# HT66FM5440_EVB.net
KiCad netlist of a schematic drawn in Altium Designer
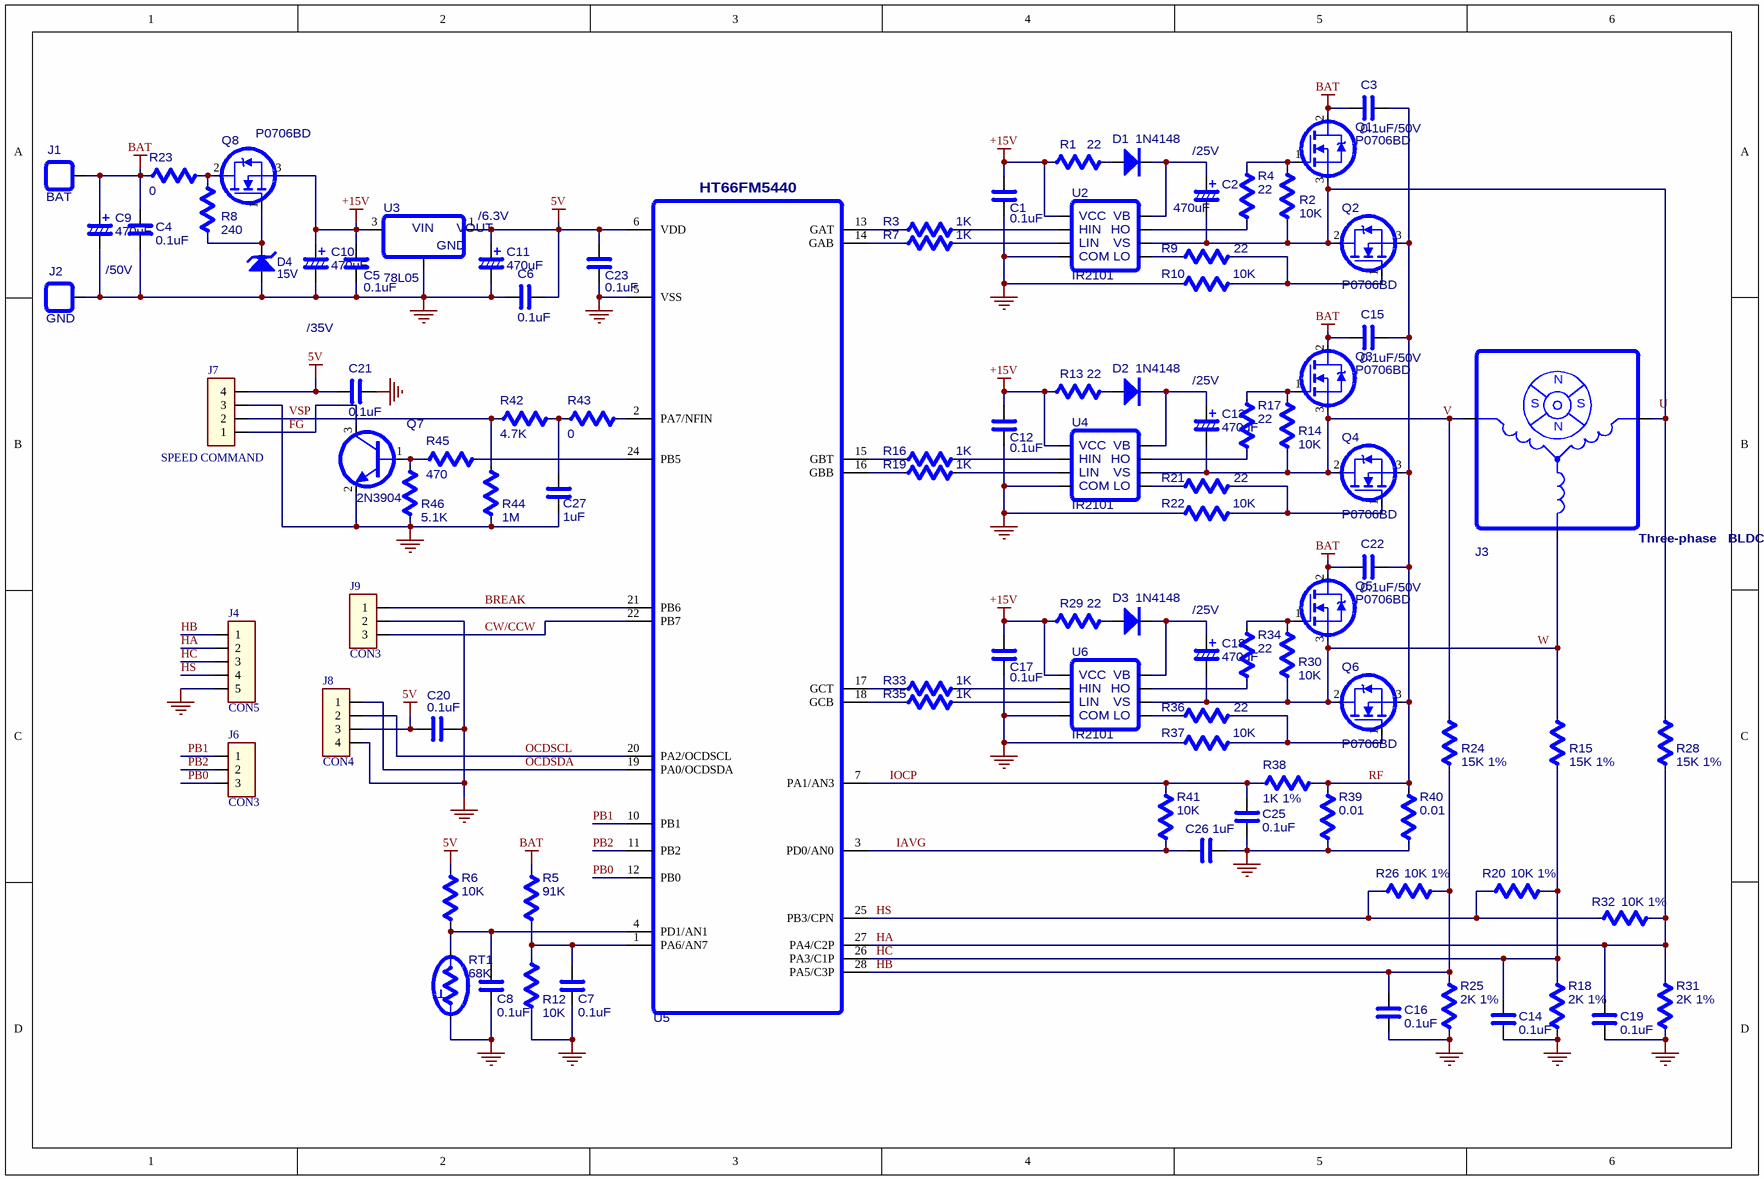
[diagram p0: HT66FM5440_EVB.SchDoc]

(export (version "E")
  (design (tool "Eeschema 10.0.6"))
  (components
    (comp (ref "C1")
      (value "0.1uF")
      (description "Capacitor")
      (fields (field (name "PUBLISHER") "Altium Limited"))
      (libsource (lib "Holtek Component Library V2") (part "Cap(1)"))
    )
    (comp (ref "C2")
      (value "470uF")
      (footprint "0805C")
      (description "Capacitor")
      (libsource (lib "C70005") (part "Cap(2)"))
    )
    (comp (ref "C3")
      (value "0.1uF/50V")
      (description "Capacitor")
      (fields (field (name "PUBLISHER") "Altium Limited"))
      (libsource (lib "Holtek Component Library V2") (part "Cap(1)"))
    )
    (comp (ref "C4")
      (value "0.1uF")
      (description "Capacitor")
      (fields (field (name "PUBLISHER") "Altium Limited"))
      (libsource (lib "Holtek Component Library V2") (part "Cap(1)"))
    )
    (comp (ref "C5")
      (value "0.1uF")
      (description "Capacitor")
      (fields (field (name "PUBLISHER") "Altium Limited"))
      (libsource (lib "Holtek Component Library V2") (part "Cap(1)"))
    )
    (comp (ref "C6")
      (value "0.1uF")
      (description "Capacitor")
      (fields (field (name "PUBLISHER") "Altium Limited"))
      (libsource (lib "Holtek Component Library V2") (part "Cap(1)"))
    )
    (comp (ref "C7")
      (value "0.1uF")
      (description "Capacitor")
      (fields (field (name "PUBLISHER") "Altium Limited"))
      (libsource (lib "Holtek Component Library V2") (part "Cap(1)"))
    )
    (comp (ref "C8")
      (value "0.1uF")
      (description "Capacitor")
      (fields (field (name "PUBLISHER") "Altium Limited"))
      (libsource (lib "Holtek Component Library V2") (part "Cap(1)"))
    )
    (comp (ref "C9")
      (value "470uF")
      (footprint "CD-10.5*21")
      (description "Capacitor")
      (libsource (lib "C70005") (part "Cap(2)"))
    )
    (comp (ref "C10")
      (value "470uF")
      (footprint "ECAP 35V47UF")
      (description "Capacitor")
      (libsource (lib "C70005") (part "Cap(2)"))
    )
    (comp (ref "C11")
      (value "470uF")
      (footprint "ECAP 35V47UF")
      (description "Capacitor")
      (libsource (lib "C70005") (part "Cap(2)"))
    )
    (comp (ref "C12")
      (value "0.1uF")
      (description "Capacitor")
      (fields (field (name "PUBLISHER") "Altium Limited"))
      (libsource (lib "Holtek Component Library V2") (part "Cap(1)"))
    )
    (comp (ref "C13")
      (value "470uF")
      (footprint "0805C")
      (description "Capacitor")
      (libsource (lib "C70005") (part "Cap(2)"))
    )
    (comp (ref "C14")
      (value "0.1uF")
      (footprint "0603C")
      (description "Capacitor")
      (fields (field (name "PUBLISHER") "Altium Limited"))
      (libsource (lib "Holtek Component Library V2") (part "Cap(1)"))
    )
    (comp (ref "C15")
      (value "0.1uF/50V")
      (description "Capacitor")
      (fields (field (name "PUBLISHER") "Altium Limited"))
      (libsource (lib "Holtek Component Library V2") (part "Cap(1)"))
    )
    (comp (ref "C16")
      (value "0.1uF")
      (footprint "0603C")
      (description "Capacitor")
      (fields (field (name "PUBLISHER") "Altium Limited"))
      (libsource (lib "Holtek Component Library V2") (part "Cap(1)"))
    )
    (comp (ref "C17")
      (value "0.1uF")
      (description "Capacitor")
      (fields (field (name "PUBLISHER") "Altium Limited"))
      (libsource (lib "Holtek Component Library V2") (part "Cap(1)"))
    )
    (comp (ref "C18")
      (value "470uF")
      (footprint "0805C")
      (description "Capacitor")
      (libsource (lib "C70005") (part "Cap(2)"))
    )
    (comp (ref "C19")
      (value "0.1uF")
      (footprint "0603C")
      (description "Capacitor")
      (fields (field (name "PUBLISHER") "Altium Limited"))
      (libsource (lib "Holtek Component Library V2") (part "Cap(1)"))
    )
    (comp (ref "C20")
      (value "0.1uF")
      (footprint "0603c")
      (description "Capacitor")
      (fields (field (name "PUBLISHER") "Altium Limited"))
      (libsource (lib "Holtek Component Library V2") (part "Cap(1)"))
    )
    (comp (ref "C21")
      (value "0.1uF")
      (footprint "0603c")
      (description "Capacitor")
      (fields (field (name "PUBLISHER") "Altium Limited"))
      (libsource (lib "Holtek Component Library V2") (part "Cap(1)"))
    )
    (comp (ref "C22")
      (value "0.1uF/50V")
      (description "Capacitor")
      (fields (field (name "PUBLISHER") "Altium Limited"))
      (libsource (lib "Holtek Component Library V2") (part "Cap(1)"))
    )
    (comp (ref "C23")
      (value "0.1uF")
      (description "Capacitor")
      (fields (field (name "PUBLISHER") "Altium Limited"))
      (libsource (lib "Holtek Component Library V2") (part "Cap(1)"))
    )
    (comp (ref "C25")
      (value "0.1uF")
      (description "Capacitor")
      (fields (field (name "PUBLISHER") "Altium Limited"))
      (libsource (lib "Holtek Component Library V2") (part "Cap(1)"))
    )
    (comp (ref "C26")
      (value "1uF")
      (description "Capacitor")
      (fields (field (name "PUBLISHER") "Altium Limited"))
      (libsource (lib "Holtek Component Library V2") (part "Cap(1)"))
    )
    (comp (ref "C27")
      (value "1uF")
      (description "Capacitor")
      (fields (field (name "PUBLISHER") "Altium Limited"))
      (libsource (lib "Holtek Component Library V2") (part "Cap(1)"))
    )
    (comp (ref "D1")
      (value "1N4148")
      (footprint "1206D")
      (description "Diode")
      (fields (field (name "PUBLISHER") "Altium Limited"))
      (libsource (lib "Holtek Component Library V2") (part "Diode(1)"))
    )
    (comp (ref "D2")
      (value "1N4148")
      (footprint "1206D")
      (description "Diode")
      (fields (field (name "PUBLISHER") "Altium Limited"))
      (libsource (lib "Holtek Component Library V2") (part "Diode(1)"))
    )
    (comp (ref "D3")
      (value "1N4148")
      (footprint "1206D")
      (description "Diode")
      (fields (field (name "PUBLISHER") "Altium Limited"))
      (libsource (lib "Holtek Component Library V2") (part "Diode(1)"))
    )
    (comp (ref "D4")
      (value "15V")
      (footprint "1206D")
      (description "Zener Diode")
      (libsource (lib "Holtek Component Library V2(Chris)") (part "Zener(1)"))
    )
    (comp (ref "J1")
      (value "BAT")
      (footprint "SIP1-big")
      (description "CON1")
      (fields (field (name "PUBLISHER") "Altium Limited"))
      (libsource (lib "C70005-A1") (part "CON1"))
    )
    (comp (ref "J2")
      (value "GND")
      (footprint "SIP1-big")
      (description "CON1")
      (fields (field (name "PUBLISHER") "Altium Limited"))
      (libsource (lib "C70005-A1") (part "CON1"))
    )
    (comp (ref "J3") (value "BLDC motor(1)") (libsource (lib "C70005") (part "BLDC motor(1)_1")))
    (comp (ref "J4") (value "CON5") (libsource (lib "MYLIB") (part "CON5")))
    (comp (ref "J6") (value "CON3") (libsource (lib "") (part "CON3_1")))
    (comp (ref "J7") (value "SPEED COMMAND") (footprint "HDR1X4") (libsource (lib "MYLIB") (part "CON4")))
    (comp (ref "J8") (value "CON4") (footprint "SIP4") (libsource (lib "") (part "CON4_1")))
    (comp (ref "J9") (value "CON3") (footprint "SIP3-2.54mm") (libsource (lib "MYLIB") (part "CON3")))
    (comp (ref "Q1")
      (value "P0706BD")
      (footprint "TO252")
      (description "N-Channel Power MOSFET")
      (fields (field (name "PUBLISHER") "Altium Limited"))
      (libsource (lib "C70005") (part "NMOS(4)"))
    )
    (comp (ref "Q2")
      (value "P0706BD")
      (footprint "TO252")
      (description "N-Channel Power MOSFET")
      (fields (field (name "PUBLISHER") "Altium Limited"))
      (libsource (lib "C70005") (part "NMOS(4)"))
    )
    (comp (ref "Q3")
      (value "P0706BD")
      (footprint "TO252")
      (description "N-Channel Power MOSFET")
      (fields (field (name "PUBLISHER") "Altium Limited"))
      (libsource (lib "C70005") (part "NMOS(4)"))
    )
    (comp (ref "Q4")
      (value "P0706BD")
      (footprint "TO252")
      (description "N-Channel Power MOSFET")
      (fields (field (name "PUBLISHER") "Altium Limited"))
      (libsource (lib "C70005") (part "NMOS(4)"))
    )
    (comp (ref "Q5")
      (value "P0706BD")
      (footprint "TO252")
      (description "N-Channel Power MOSFET")
      (fields (field (name "PUBLISHER") "Altium Limited"))
      (libsource (lib "C70005") (part "NMOS(4)"))
    )
    (comp (ref "Q6")
      (value "P0706BD")
      (footprint "TO252")
      (description "N-Channel Power MOSFET")
      (fields (field (name "PUBLISHER") "Altium Limited"))
      (libsource (lib "C70005") (part "NMOS(4)"))
    )
    (comp (ref "Q7")
      (value "2N3904")
      (footprint "SOT-23")
      (description "NPN Bipolar Transistor")
      (fields (field (name "PUBLISHER") "Altium Limited"))
      (libsource (lib "C70005") (part "NPN(2)"))
    )
    (comp (ref "Q8")
      (value "P0706BD")
      (footprint "TO252")
      (description "N-Channel Power MOSFET")
      (fields (field (name "PUBLISHER") "Altium Limited"))
      (libsource (lib "C70005") (part "NMOS(4)"))
    )
    (comp (ref "R1")
      (value "22")
      (description "Resisitor")
      (libsource (lib "Holtek Component Library V2") (part "Resistor(1)_1"))
    )
    (comp (ref "R2")
      (value "10K")
      (description "Resisitor")
      (libsource (lib "Holtek Component Library V2") (part "Resistor(1)_1"))
    )
    (comp (ref "R3")
      (value "1K")
      (description "Resisitor")
      (libsource (lib "Holtek Component Library V2") (part "Resistor(1)_1"))
    )
    (comp (ref "R4")
      (value "22")
      (description "Resisitor")
      (libsource (lib "Holtek Component Library V2") (part "Resistor(1)_1"))
    )
    (comp (ref "R5")
      (value "91K")
      (description "Resisitor")
      (libsource (lib "Holtek Component Library V2") (part "Resistor(1)_1"))
    )
    (comp (ref "R6")
      (value "10K")
      (description "Resisitor")
      (libsource (lib "Holtek Component Library V2") (part "Resistor(1)_1"))
    )
    (comp (ref "R7")
      (value "1K")
      (description "Resisitor")
      (libsource (lib "Holtek Component Library V2") (part "Resistor(1)_1"))
    )
    (comp (ref "R8")
      (value "240")
      (description "Resisitor")
      (libsource (lib "Holtek Component Library V2") (part "Resistor(1)_1"))
    )
    (comp (ref "R9")
      (value "22")
      (description "Resisitor")
      (libsource (lib "Holtek Component Library V2") (part "Resistor(1)_1"))
    )
    (comp (ref "R10")
      (value "10K")
      (description "Resisitor")
      (libsource (lib "Holtek Component Library V2") (part "Resistor(1)_1"))
    )
    (comp (ref "R12")
      (value "10K")
      (description "Resisitor")
      (libsource (lib "Holtek Component Library V2") (part "Resistor(1)_1"))
    )
    (comp (ref "R13")
      (value "22")
      (description "Resisitor")
      (libsource (lib "Holtek Component Library V2") (part "Resistor(1)_1"))
    )
    (comp (ref "R14")
      (value "10K")
      (description "Resisitor")
      (libsource (lib "Holtek Component Library V2") (part "Resistor(1)_1"))
    )
    (comp (ref "R15")
      (value "15K 1%")
      (description "Resisitor")
      (libsource (lib "Holtek Component Library V2") (part "Resistor(1)_1"))
    )
    (comp (ref "R16")
      (value "1K")
      (description "Resisitor")
      (libsource (lib "Holtek Component Library V2") (part "Resistor(1)_1"))
    )
    (comp (ref "R17")
      (value "22")
      (description "Resisitor")
      (libsource (lib "Holtek Component Library V2") (part "Resistor(1)_1"))
    )
    (comp (ref "R18")
      (value "2K 1%")
      (description "Resisitor")
      (libsource (lib "Holtek Component Library V2") (part "Resistor(1)_1"))
    )
    (comp (ref "R19")
      (value "1K")
      (description "Resisitor")
      (libsource (lib "Holtek Component Library V2") (part "Resistor(1)_1"))
    )
    (comp (ref "R20")
      (value "10K 1%")
      (description "Resisitor")
      (libsource (lib "Holtek Component Library V2") (part "Resistor(1)_1"))
    )
    (comp (ref "R21")
      (value "22")
      (description "Resisitor")
      (libsource (lib "Holtek Component Library V2") (part "Resistor(1)_1"))
    )
    (comp (ref "R22")
      (value "10K")
      (description "Resisitor")
      (libsource (lib "Holtek Component Library V2") (part "Resistor(1)_1"))
    )
    (comp (ref "R23")
      (value "0")
      (description "Resisitor")
      (libsource (lib "Holtek Component Library V2") (part "Resistor(1)_1"))
    )
    (comp (ref "R24")
      (value "15K 1%")
      (description "Resisitor")
      (libsource (lib "Holtek Component Library V2") (part "Resistor(1)_1"))
    )
    (comp (ref "R25")
      (value "2K 1%")
      (description "Resisitor")
      (libsource (lib "Holtek Component Library V2") (part "Resistor(1)_1"))
    )
    (comp (ref "R26")
      (value "10K 1%")
      (description "Resisitor")
      (libsource (lib "Holtek Component Library V2") (part "Resistor(1)_1"))
    )
    (comp (ref "R28")
      (value "15K 1%")
      (description "Resisitor")
      (libsource (lib "Holtek Component Library V2") (part "Resistor(1)_1"))
    )
    (comp (ref "R29")
      (value "22")
      (description "Resisitor")
      (libsource (lib "Holtek Component Library V2") (part "Resistor(1)_1"))
    )
    (comp (ref "R30")
      (value "10K")
      (description "Resisitor")
      (libsource (lib "Holtek Component Library V2") (part "Resistor(1)_1"))
    )
    (comp (ref "R31")
      (value "2K 1%")
      (description "Resisitor")
      (libsource (lib "Holtek Component Library V2") (part "Resistor(1)_1"))
    )
    (comp (ref "R32")
      (value "10K 1%")
      (description "Resisitor")
      (libsource (lib "Holtek Component Library V2") (part "Resistor(1)_1"))
    )
    (comp (ref "R33")
      (value "1K")
      (description "Resisitor")
      (libsource (lib "Holtek Component Library V2") (part "Resistor(1)_1"))
    )
    (comp (ref "R34")
      (value "22")
      (description "Resisitor")
      (libsource (lib "Holtek Component Library V2") (part "Resistor(1)_1"))
    )
    (comp (ref "R35")
      (value "1K")
      (description "Resisitor")
      (libsource (lib "Holtek Component Library V2") (part "Resistor(1)_1"))
    )
    (comp (ref "R36")
      (value "22")
      (description "Resisitor")
      (libsource (lib "Holtek Component Library V2") (part "Resistor(1)_1"))
    )
    (comp (ref "R37")
      (value "10K")
      (description "Resisitor")
      (libsource (lib "Holtek Component Library V2") (part "Resistor(1)_1"))
    )
    (comp (ref "R38")
      (value "1K 1%")
      (description "Resisitor")
      (libsource (lib "Holtek Component Library V2") (part "Resistor(1)_1"))
    )
    (comp (ref "R39")
      (value "0.01")
      (description "Resisitor")
      (libsource (lib "Holtek Component Library V2") (part "Resistor(1)_1"))
    )
    (comp (ref "R40")
      (value "0.01")
      (description "Resisitor")
      (libsource (lib "Holtek Component Library V2") (part "Resistor(1)_1"))
    )
    (comp (ref "R41")
      (value "10K")
      (description "Resisitor")
      (libsource (lib "Holtek Component Library V2") (part "Resistor(1)_1"))
    )
    (comp (ref "R42")
      (value "4.7K")
      (description "Resisitor")
      (libsource (lib "Holtek Component Library V2") (part "Resistor(1)_1"))
    )
    (comp (ref "R43")
      (value "0")
      (description "Resisitor")
      (libsource (lib "Holtek Component Library V2") (part "Resistor(1)_1"))
    )
    (comp (ref "R44")
      (value "1M")
      (description "Resisitor")
      (libsource (lib "Holtek Component Library V2") (part "Resistor(1)_1"))
    )
    (comp (ref "R45")
      (value "470")
      (description "Resisitor")
      (libsource (lib "Holtek Component Library V2") (part "Resistor(1)_1"))
    )
    (comp (ref "R46")
      (value "5.1K")
      (description "Resisitor")
      (libsource (lib "Holtek Component Library V2") (part "Resistor(1)_1"))
    )
    (comp (ref "RT1") (value "68K") (libsource (lib "Holtek Component Library V2") (part "Sensor(1)")))
    (comp (ref "U2") (value "IR2101") (footprint "SOP-8") (libsource (lib "C70005") (part "IR2101/SOP-8")))
    (comp (ref "U3") (value "78L05") (footprint "SOT-89") (libsource (lib "C70005") (part "78L05_1")))
    (comp (ref "U4") (value "IR2101") (footprint "SOP-8") (libsource (lib "C70005") (part "IR2101/SOP-8")))
    (comp (ref "U5")
      (value "HT66FM5440/28SSOP")
      (footprint "SSOP28")
      (libsource (lib "C70005") (part "HT66FM5440/28SSOP"))
    )
    (comp (ref "U6") (value "IR2101") (footprint "SOP-8") (libsource (lib "C70005") (part "IR2101/SOP-8")))
  )
  (nets
    (net (code "1") (name "+15V") (class "Default")
      (node (ref "C1") (pin "2") (pinfunction "2_2") (pintype "passive"))
      (node (ref "C10") (pin "1") (pinfunction "1_1") (pintype "passive"))
      (node (ref "C12") (pin "2") (pinfunction "2_2") (pintype "passive"))
      (node (ref "C17") (pin "2") (pinfunction "2_2") (pintype "passive"))
      (node (ref "C5") (pin "2") (pinfunction "2_2") (pintype "passive"))
      (node (ref "Q8") (pin "3") (pinfunction "60_3") (pintype "passive"))
      (node (ref "R1") (pin "1") (pinfunction "1_1") (pintype "passive"))
      (node (ref "R13") (pin "1") (pinfunction "1_1") (pintype "passive"))
      (node (ref "R29") (pin "1") (pinfunction "1_1") (pintype "passive"))
      (node (ref "U2") (pin "1") (pinfunction "VCC_1") (pintype "passive"))
      (node (ref "U3") (pin "3") (pinfunction "Vin_3") (pintype "passive"))
      (node (ref "U4") (pin "1") (pinfunction "VCC_1") (pintype "passive"))
      (node (ref "U6") (pin "1") (pinfunction "VCC_1") (pintype "passive"))
    )
    (net (code "2") (name "/BREAK") (class "Default")
      (node (ref "J9") (pin "1") (pinfunction "1_1") (pintype "passive"))
      (node (ref "U5") (pin "21") (pinfunction "PB6_21") (pintype "passive"))
    )
    (net (code "3") (name "/CW{slash}CCW") (class "Default")
      (node (ref "J9") (pin "3") (pinfunction "3_3") (pintype "passive"))
      (node (ref "U5") (pin "22") (pinfunction "PB7_22") (pintype "passive"))
    )
    (net (code "4") (name "/FG") (class "Default")
      (node (ref "J7") (pin "1") (pinfunction "1_1") (pintype "passive"))
      (node (ref "Q7") (pin "3") (pinfunction "C_3") (pintype "passive"))
    )
    (net (code "5") (name "/HA") (class "Default")
      (node (ref "C19") (pin "1") (pinfunction "1_1") (pintype "passive"))
      (node (ref "J4") (pin "2") (pinfunction "2_2") (pintype "passive"))
      (node (ref "R28") (pin "2") (pinfunction "2_2") (pintype "passive"))
      (node (ref "R31") (pin "2") (pinfunction "2_2") (pintype "passive"))
      (node (ref "R32") (pin "2") (pinfunction "2_2") (pintype "passive"))
      (node (ref "U5") (pin "27") (pinfunction "PA4/C2P_27") (pintype "passive"))
    )
    (net (code "6") (name "/HB") (class "Default")
      (node (ref "C16") (pin "1") (pinfunction "1_1") (pintype "passive"))
      (node (ref "J4") (pin "1") (pinfunction "1_1") (pintype "passive"))
      (node (ref "R24") (pin "2") (pinfunction "2_2") (pintype "passive"))
      (node (ref "R25") (pin "2") (pinfunction "2_2") (pintype "passive"))
      (node (ref "R26") (pin "2") (pinfunction "2_2") (pintype "passive"))
      (node (ref "U5") (pin "28") (pinfunction "PA5/C3P_28") (pintype "passive"))
    )
    (net (code "7") (name "/HC") (class "Default")
      (node (ref "C14") (pin "1") (pinfunction "1_1") (pintype "passive"))
      (node (ref "J4") (pin "3") (pinfunction "3_3") (pintype "passive"))
      (node (ref "R15") (pin "2") (pinfunction "2_2") (pintype "passive"))
      (node (ref "R18") (pin "2") (pinfunction "2_2") (pintype "passive"))
      (node (ref "R20") (pin "2") (pinfunction "2_2") (pintype "passive"))
      (node (ref "U5") (pin "26") (pinfunction "PA3/C1P_26") (pintype "passive"))
    )
    (net (code "8") (name "/HS") (class "Default")
      (node (ref "J4") (pin "4") (pinfunction "4_4") (pintype "passive"))
      (node (ref "R20") (pin "1") (pinfunction "1_1") (pintype "passive"))
      (node (ref "R26") (pin "1") (pinfunction "1_1") (pintype "passive"))
      (node (ref "R32") (pin "1") (pinfunction "1_1") (pintype "passive"))
      (node (ref "U5") (pin "25") (pinfunction "PB3/CPN_25") (pintype "passive"))
    )
    (net (code "9") (name "/IAVG") (class "Default")
      (node (ref "C26") (pin "2") (pinfunction "2_2") (pintype "passive"))
      (node (ref "R41") (pin "1") (pinfunction "1_1") (pintype "passive"))
      (node (ref "U5") (pin "3") (pinfunction "PD0/AN0_3") (pintype "passive"))
    )
    (net (code "10") (name "/IOCP") (class "Default")
      (node (ref "C25") (pin "2") (pinfunction "2_2") (pintype "passive"))
      (node (ref "R38") (pin "1") (pinfunction "1_1") (pintype "passive"))
      (node (ref "R41") (pin "2") (pinfunction "2_2") (pintype "passive"))
      (node (ref "U5") (pin "7") (pinfunction "PA1/AN3_7") (pintype "passive"))
    )
    (net (code "11") (name "/OCDSCL") (class "Default")
      (node (ref "J8") (pin "2") (pinfunction "2_2") (pintype "passive"))
      (node (ref "U5") (pin "20") (pinfunction "PA2/OCDSCL_20") (pintype "passive"))
    )
    (net (code "12") (name "/OCDSDA") (class "Default")
      (node (ref "J8") (pin "1") (pinfunction "1_1") (pintype "passive"))
      (node (ref "U5") (pin "19") (pinfunction "PA0/OCDSDA_19") (pintype "passive"))
    )
    (net (code "13") (name "/PB0") (class "Default")
      (node (ref "J6") (pin "3") (pinfunction "3_3") (pintype "passive"))
      (node (ref "U5") (pin "12") (pinfunction "PB0_12") (pintype "passive"))
    )
    (net (code "14") (name "/PB1") (class "Default")
      (node (ref "J6") (pin "1") (pinfunction "1_1") (pintype "passive"))
      (node (ref "U5") (pin "10") (pinfunction "PB1_10") (pintype "passive"))
    )
    (net (code "15") (name "/PB2") (class "Default")
      (node (ref "J6") (pin "2") (pinfunction "2_2") (pintype "passive"))
      (node (ref "U5") (pin "11") (pinfunction "PB2_11") (pintype "passive"))
    )
    (net (code "16") (name "/RF") (class "Default")
      (node (ref "C15") (pin "2") (pinfunction "2_2") (pintype "passive"))
      (node (ref "C22") (pin "2") (pinfunction "2_2") (pintype "passive"))
      (node (ref "C3") (pin "2") (pinfunction "2_2") (pintype "passive"))
      (node (ref "Q2") (pin "3") (pinfunction "60_3") (pintype "passive"))
      (node (ref "Q4") (pin "3") (pinfunction "60_3") (pintype "passive"))
      (node (ref "Q6") (pin "3") (pinfunction "60_3") (pintype "passive"))
      (node (ref "R38") (pin "2") (pinfunction "2_2") (pintype "passive"))
      (node (ref "R39") (pin "2") (pinfunction "2_2") (pintype "passive"))
      (node (ref "R40") (pin "2") (pinfunction "2_2") (pintype "passive"))
    )
    (net (code "18") (name "/V") (class "Default")
      (node (ref "C13") (pin "2") (pinfunction "2_2") (pintype "passive"))
      (node (ref "J3") (pin "2") (pinfunction "2_2") (pintype "passive"))
      (node (ref "Q3") (pin "3") (pinfunction "60_3") (pintype "passive"))
      (node (ref "Q4") (pin "2") (pinfunction "D_2") (pintype "passive"))
      (node (ref "R14") (pin "1") (pinfunction "1_1") (pintype "passive"))
      (node (ref "R24") (pin "1") (pinfunction "1_1") (pintype "passive"))
      (node (ref "U4") (pin "6") (pinfunction "VS_6") (pintype "passive"))
    )
    (net (code "19") (name "/VSP") (class "Default")
      (node (ref "J7") (pin "2") (pinfunction "2_2") (pintype "passive"))
      (node (ref "R42") (pin "1") (pinfunction "1_1") (pintype "passive"))
      (node (ref "R44") (pin "2") (pinfunction "2_2") (pintype "passive"))
    )
    (net (code "20") (name "/W") (class "Default")
      (node (ref "C18") (pin "2") (pinfunction "2_2") (pintype "passive"))
      (node (ref "J3") (pin "3") (pinfunction "3_3") (pintype "passive"))
      (node (ref "Q5") (pin "3") (pinfunction "60_3") (pintype "passive"))
      (node (ref "Q6") (pin "2") (pinfunction "D_2") (pintype "passive"))
      (node (ref "R15") (pin "1") (pinfunction "1_1") (pintype "passive"))
      (node (ref "R30") (pin "1") (pinfunction "1_1") (pintype "passive"))
      (node (ref "U6") (pin "6") (pinfunction "VS_6") (pintype "passive"))
    )
    (net (code "21") (name "5V") (class "Default")
      (node (ref "C11") (pin "1") (pinfunction "1_1") (pintype "passive"))
      (node (ref "C20") (pin "1") (pinfunction "1_1") (pintype "passive"))
      (node (ref "C21") (pin "2") (pinfunction "2_2") (pintype "passive"))
      (node (ref "C23") (pin "1") (pinfunction "1_1") (pintype "passive"))
      (node (ref "C6") (pin "2") (pinfunction "2_2") (pintype "passive"))
      (node (ref "J7") (pin "4") (pinfunction "4_4") (pintype "passive"))
      (node (ref "J8") (pin "3") (pinfunction "3_3") (pintype "passive"))
      (node (ref "R6") (pin "2") (pinfunction "2_2") (pintype "passive"))
      (node (ref "U3") (pin "1") (pinfunction "Vout_1") (pintype "passive"))
      (node (ref "U5") (pin "6") (pinfunction "VDD_6") (pintype "passive"))
    )
    (net (code "22") (name "BAT") (class "Default")
      (node (ref "C15") (pin "1") (pinfunction "1_1") (pintype "passive"))
      (node (ref "C22") (pin "1") (pinfunction "1_1") (pintype "passive"))
      (node (ref "C3") (pin "1") (pinfunction "1_1") (pintype "passive"))
      (node (ref "C4") (pin "1") (pinfunction "1_1") (pintype "passive"))
      (node (ref "C9") (pin "1") (pinfunction "1_1") (pintype "passive"))
      (node (ref "J1") (pin "1") (pinfunction "1_1") (pintype "passive"))
      (node (ref "Q1") (pin "2") (pinfunction "D_2") (pintype "passive"))
      (node (ref "Q3") (pin "2") (pinfunction "D_2") (pintype "passive"))
      (node (ref "Q5") (pin "2") (pinfunction "D_2") (pintype "passive"))
      (node (ref "R23") (pin "1") (pinfunction "1_1") (pintype "passive"))
      (node (ref "R5") (pin "2") (pinfunction "2_2") (pintype "passive"))
    )
    (net (code "23") (name "GND") (class "Default")
      (node (ref "C1") (pin "1") (pinfunction "1_1") (pintype "passive"))
      (node (ref "C10") (pin "2") (pinfunction "2_2") (pintype "passive"))
      (node (ref "C11") (pin "2") (pinfunction "2_2") (pintype "passive"))
      (node (ref "C12") (pin "1") (pinfunction "1_1") (pintype "passive"))
      (node (ref "C14") (pin "2") (pinfunction "2_2") (pintype "passive"))
      (node (ref "C16") (pin "2") (pinfunction "2_2") (pintype "passive"))
      (node (ref "C17") (pin "1") (pinfunction "1_1") (pintype "passive"))
      (node (ref "C19") (pin "2") (pinfunction "2_2") (pintype "passive"))
      (node (ref "C20") (pin "2") (pinfunction "2_2") (pintype "passive"))
      (node (ref "C21") (pin "1") (pinfunction "1_1") (pintype "passive"))
      (node (ref "C23") (pin "2") (pinfunction "2_2") (pintype "passive"))
      (node (ref "C25") (pin "1") (pinfunction "1_1") (pintype "passive"))
      (node (ref "C26") (pin "1") (pinfunction "1_1") (pintype "passive"))
      (node (ref "C27") (pin "1") (pinfunction "1_1") (pintype "passive"))
      (node (ref "C4") (pin "2") (pinfunction "2_2") (pintype "passive"))
      (node (ref "C5") (pin "1") (pinfunction "1_1") (pintype "passive"))
      (node (ref "C6") (pin "1") (pinfunction "1_1") (pintype "passive"))
      (node (ref "C7") (pin "1") (pinfunction "1_1") (pintype "passive"))
      (node (ref "C8") (pin "1") (pinfunction "1_1") (pintype "passive"))
      (node (ref "C9") (pin "2") (pinfunction "2_2") (pintype "passive"))
      (node (ref "D4") (pin "1") (pinfunction "A_1") (pintype "passive"))
      (node (ref "J2") (pin "1") (pinfunction "1_1") (pintype "passive"))
      (node (ref "J4") (pin "5") (pinfunction "5_5") (pintype "passive"))
      (node (ref "J7") (pin "3") (pinfunction "3_3") (pintype "passive"))
      (node (ref "J8") (pin "4") (pinfunction "4_4") (pintype "passive"))
      (node (ref "J9") (pin "2") (pinfunction "2_2") (pintype "passive"))
      (node (ref "Q7") (pin "2") (pinfunction "E_2") (pintype "passive"))
      (node (ref "R10") (pin "2") (pinfunction "2_2") (pintype "passive"))
      (node (ref "R12") (pin "1") (pinfunction "1_1") (pintype "passive"))
      (node (ref "R18") (pin "1") (pinfunction "1_1") (pintype "passive"))
      (node (ref "R22") (pin "2") (pinfunction "2_2") (pintype "passive"))
      (node (ref "R25") (pin "1") (pinfunction "1_1") (pintype "passive"))
      (node (ref "R31") (pin "1") (pinfunction "1_1") (pintype "passive"))
      (node (ref "R37") (pin "2") (pinfunction "2_2") (pintype "passive"))
      (node (ref "R39") (pin "1") (pinfunction "1_1") (pintype "passive"))
      (node (ref "R40") (pin "1") (pinfunction "1_1") (pintype "passive"))
      (node (ref "R44") (pin "1") (pinfunction "1_1") (pintype "passive"))
      (node (ref "R46") (pin "1") (pinfunction "1_1") (pintype "passive"))
      (node (ref "RT1") (pin "1") (pinfunction "1_1") (pintype "passive"))
      (node (ref "U2") (pin "4") (pinfunction "COM_4") (pintype "passive"))
      (node (ref "U3") (pin "2") (pinfunction "GND_2") (pintype "passive"))
      (node (ref "U4") (pin "4") (pinfunction "COM_4") (pintype "passive"))
      (node (ref "U5") (pin "5") (pinfunction "VSS_5") (pintype "passive"))
      (node (ref "U6") (pin "4") (pinfunction "COM_4") (pintype "passive"))
    )
    (net (code "24") (name "Net-(C27-Pad2)") (class "Default")
      (node (ref "C27") (pin "2") (pinfunction "2_2") (pintype "passive"))
      (node (ref "R42") (pin "2") (pinfunction "2_2") (pintype "passive"))
      (node (ref "R43") (pin "1") (pinfunction "1_1") (pintype "passive"))
    )
    (net (code "25") (name "Net-(D1-A)") (class "Default")
      (node (ref "D1") (pin "1") (pinfunction "A_1") (pintype "passive"))
      (node (ref "R1") (pin "2") (pinfunction "2_2") (pintype "passive"))
    )
    (net (code "26") (name "Net-(D1-K)") (class "Default")
      (node (ref "C2") (pin "1") (pinfunction "1_1") (pintype "passive"))
      (node (ref "D1") (pin "2") (pinfunction "K_2") (pintype "passive"))
      (node (ref "U2") (pin "8") (pinfunction "VB_8") (pintype "passive"))
    )
    (net (code "27") (name "Net-(D2-A)") (class "Default")
      (node (ref "D2") (pin "1") (pinfunction "A_1") (pintype "passive"))
      (node (ref "R13") (pin "2") (pinfunction "2_2") (pintype "passive"))
    )
    (net (code "28") (name "Net-(D2-K)") (class "Default")
      (node (ref "C13") (pin "1") (pinfunction "1_1") (pintype "passive"))
      (node (ref "D2") (pin "2") (pinfunction "K_2") (pintype "passive"))
      (node (ref "U4") (pin "8") (pinfunction "VB_8") (pintype "passive"))
    )
    (net (code "29") (name "Net-(D3-A)") (class "Default")
      (node (ref "D3") (pin "1") (pinfunction "A_1") (pintype "passive"))
      (node (ref "R29") (pin "2") (pinfunction "2_2") (pintype "passive"))
    )
    (net (code "30") (name "Net-(D3-K)") (class "Default")
      (node (ref "C18") (pin "1") (pinfunction "1_1") (pintype "passive"))
      (node (ref "D3") (pin "2") (pinfunction "K_2") (pintype "passive"))
      (node (ref "U6") (pin "8") (pinfunction "VB_8") (pintype "passive"))
    )
    (net (code "31") (name "Net-(D4-K)") (class "Default")
      (node (ref "D4") (pin "2") (pinfunction "K_2") (pintype "passive"))
      (node (ref "Q8") (pin "1") (pinfunction "G_1") (pintype "passive"))
      (node (ref "R8") (pin "1") (pinfunction "1_1") (pintype "passive"))
    )
    (net (code "32") (name "Net-(Q1-60)") (class "Default")
      (node (ref "C2") (pin "2") (pinfunction "2_2") (pintype "passive"))
      (node (ref "J3") (pin "1") (pinfunction "1_1") (pintype "passive"))
      (node (ref "Q1") (pin "3") (pinfunction "60_3") (pintype "passive"))
      (node (ref "Q2") (pin "2") (pinfunction "D_2") (pintype "passive"))
      (node (ref "R2") (pin "1") (pinfunction "1_1") (pintype "passive"))
      (node (ref "R28") (pin "1") (pinfunction "1_1") (pintype "passive"))
      (node (ref "U2") (pin "6") (pinfunction "VS_6") (pintype "passive"))
    )
    (net (code "33") (name "Net-(Q1-G)") (class "Default")
      (node (ref "Q1") (pin "1") (pinfunction "G_1") (pintype "passive"))
      (node (ref "R2") (pin "2") (pinfunction "2_2") (pintype "passive"))
      (node (ref "R4") (pin "1") (pinfunction "1_1") (pintype "passive"))
    )
    (net (code "34") (name "Net-(Q2-G)") (class "Default")
      (node (ref "Q2") (pin "1") (pinfunction "G_1") (pintype "passive"))
      (node (ref "R10") (pin "1") (pinfunction "1_1") (pintype "passive"))
      (node (ref "R9") (pin "2") (pinfunction "2_2") (pintype "passive"))
    )
    (net (code "35") (name "Net-(Q3-G)") (class "Default")
      (node (ref "Q3") (pin "1") (pinfunction "G_1") (pintype "passive"))
      (node (ref "R14") (pin "2") (pinfunction "2_2") (pintype "passive"))
      (node (ref "R17") (pin "1") (pinfunction "1_1") (pintype "passive"))
    )
    (net (code "36") (name "Net-(Q4-G)") (class "Default")
      (node (ref "Q4") (pin "1") (pinfunction "G_1") (pintype "passive"))
      (node (ref "R21") (pin "2") (pinfunction "2_2") (pintype "passive"))
      (node (ref "R22") (pin "1") (pinfunction "1_1") (pintype "passive"))
    )
    (net (code "37") (name "Net-(Q5-G)") (class "Default")
      (node (ref "Q5") (pin "1") (pinfunction "G_1") (pintype "passive"))
      (node (ref "R30") (pin "2") (pinfunction "2_2") (pintype "passive"))
      (node (ref "R34") (pin "1") (pinfunction "1_1") (pintype "passive"))
    )
    (net (code "38") (name "Net-(Q6-G)") (class "Default")
      (node (ref "Q6") (pin "1") (pinfunction "G_1") (pintype "passive"))
      (node (ref "R36") (pin "2") (pinfunction "2_2") (pintype "passive"))
      (node (ref "R37") (pin "1") (pinfunction "1_1") (pintype "passive"))
    )
    (net (code "39") (name "Net-(Q7-B)") (class "Default")
      (node (ref "Q7") (pin "1") (pinfunction "B_1") (pintype "passive"))
      (node (ref "R45") (pin "1") (pinfunction "1_1") (pintype "passive"))
      (node (ref "R46") (pin "2") (pinfunction "2_2") (pintype "passive"))
    )
    (net (code "40") (name "Net-(Q8-D)") (class "Default")
      (node (ref "Q8") (pin "2") (pinfunction "D_2") (pintype "passive"))
      (node (ref "R23") (pin "2") (pinfunction "2_2") (pintype "passive"))
      (node (ref "R8") (pin "2") (pinfunction "2_2") (pintype "passive"))
    )
    (net (code "41") (name "Net-(U2-HIN)") (class "Default")
      (node (ref "R3") (pin "2") (pinfunction "2_2") (pintype "passive"))
      (node (ref "U2") (pin "2") (pinfunction "HIN_2") (pintype "passive"))
    )
    (net (code "42") (name "Net-(U2-HO)") (class "Default")
      (node (ref "R4") (pin "2") (pinfunction "2_2") (pintype "passive"))
      (node (ref "U2") (pin "7") (pinfunction "HO_7") (pintype "passive"))
    )
    (net (code "43") (name "Net-(U2-LIN)") (class "Default")
      (node (ref "R7") (pin "2") (pinfunction "2_2") (pintype "passive"))
      (node (ref "U2") (pin "3") (pinfunction "LIN_3") (pintype "passive"))
    )
    (net (code "44") (name "Net-(U2-LO)") (class "Default")
      (node (ref "R9") (pin "1") (pinfunction "1_1") (pintype "passive"))
      (node (ref "U2") (pin "5") (pinfunction "LO_5") (pintype "passive"))
    )
    (net (code "45") (name "Net-(U4-HIN)") (class "Default")
      (node (ref "R16") (pin "2") (pinfunction "2_2") (pintype "passive"))
      (node (ref "U4") (pin "2") (pinfunction "HIN_2") (pintype "passive"))
    )
    (net (code "46") (name "Net-(U4-HO)") (class "Default")
      (node (ref "R17") (pin "2") (pinfunction "2_2") (pintype "passive"))
      (node (ref "U4") (pin "7") (pinfunction "HO_7") (pintype "passive"))
    )
    (net (code "47") (name "Net-(U4-LIN)") (class "Default")
      (node (ref "R19") (pin "2") (pinfunction "2_2") (pintype "passive"))
      (node (ref "U4") (pin "3") (pinfunction "LIN_3") (pintype "passive"))
    )
    (net (code "48") (name "Net-(U4-LO)") (class "Default")
      (node (ref "R21") (pin "1") (pinfunction "1_1") (pintype "passive"))
      (node (ref "U4") (pin "5") (pinfunction "LO_5") (pintype "passive"))
    )
    (net (code "49") (name "Net-(U5-GAB)") (class "Default")
      (node (ref "R7") (pin "1") (pinfunction "1_1") (pintype "passive"))
      (node (ref "U5") (pin "14") (pinfunction "GAB_14") (pintype "passive"))
    )
    (net (code "50") (name "Net-(U5-GAT)") (class "Default")
      (node (ref "R3") (pin "1") (pinfunction "1_1") (pintype "passive"))
      (node (ref "U5") (pin "13") (pinfunction "GAT_13") (pintype "passive"))
    )
    (net (code "51") (name "Net-(U5-GBB)") (class "Default")
      (node (ref "R19") (pin "1") (pinfunction "1_1") (pintype "passive"))
      (node (ref "U5") (pin "16") (pinfunction "GBB_16") (pintype "passive"))
    )
    (net (code "52") (name "Net-(U5-GBT)") (class "Default")
      (node (ref "R16") (pin "1") (pinfunction "1_1") (pintype "passive"))
      (node (ref "U5") (pin "15") (pinfunction "GBT_15") (pintype "passive"))
    )
    (net (code "53") (name "Net-(U5-GCB)") (class "Default")
      (node (ref "R35") (pin "1") (pinfunction "1_1") (pintype "passive"))
      (node (ref "U5") (pin "18") (pinfunction "GCB_18") (pintype "passive"))
    )
    (net (code "54") (name "Net-(U5-GCT)") (class "Default")
      (node (ref "R33") (pin "1") (pinfunction "1_1") (pintype "passive"))
      (node (ref "U5") (pin "17") (pinfunction "GCT_17") (pintype "passive"))
    )
    (net (code "55") (name "Net-(U5-PA6{slash}AN7)") (class "Default")
      (node (ref "C7") (pin "2") (pinfunction "2_2") (pintype "passive"))
      (node (ref "R12") (pin "2") (pinfunction "2_2") (pintype "passive"))
      (node (ref "R5") (pin "1") (pinfunction "1_1") (pintype "passive"))
      (node (ref "U5") (pin "1") (pinfunction "PA6/AN7_1") (pintype "passive"))
    )
    (net (code "56") (name "Net-(U5-PA7{slash}NFIN)") (class "Default")
      (node (ref "R43") (pin "2") (pinfunction "2_2") (pintype "passive"))
      (node (ref "U5") (pin "2") (pinfunction "PA7/NFIN_2") (pintype "passive"))
    )
    (net (code "57") (name "Net-(U5-PB5)") (class "Default")
      (node (ref "R45") (pin "2") (pinfunction "2_2") (pintype "passive"))
      (node (ref "U5") (pin "24") (pinfunction "PB5_24") (pintype "passive"))
    )
    (net (code "58") (name "Net-(U5-PD1{slash}AN1)") (class "Default")
      (node (ref "C8") (pin "2") (pinfunction "2_2") (pintype "passive"))
      (node (ref "R6") (pin "1") (pinfunction "1_1") (pintype "passive"))
      (node (ref "RT1") (pin "2") (pinfunction "2_2") (pintype "passive"))
      (node (ref "U5") (pin "4") (pinfunction "PD1/AN1_4") (pintype "passive"))
    )
    (net (code "59") (name "Net-(U6-HIN)") (class "Default")
      (node (ref "R33") (pin "2") (pinfunction "2_2") (pintype "passive"))
      (node (ref "U6") (pin "2") (pinfunction "HIN_2") (pintype "passive"))
    )
    (net (code "60") (name "Net-(U6-HO)") (class "Default")
      (node (ref "R34") (pin "2") (pinfunction "2_2") (pintype "passive"))
      (node (ref "U6") (pin "7") (pinfunction "HO_7") (pintype "passive"))
    )
    (net (code "61") (name "Net-(U6-LIN)") (class "Default")
      (node (ref "R35") (pin "2") (pinfunction "2_2") (pintype "passive"))
      (node (ref "U6") (pin "3") (pinfunction "LIN_3") (pintype "passive"))
    )
    (net (code "62") (name "Net-(U6-LO)") (class "Default")
      (node (ref "R36") (pin "1") (pinfunction "1_1") (pintype "passive"))
      (node (ref "U6") (pin "5") (pinfunction "LO_5") (pintype "passive"))
    )
  )
)
